# P19_M_2_KEY_M_SSD_WI-FI_BT.net
KiCad netlist of a schematic drawn in Altium Designer
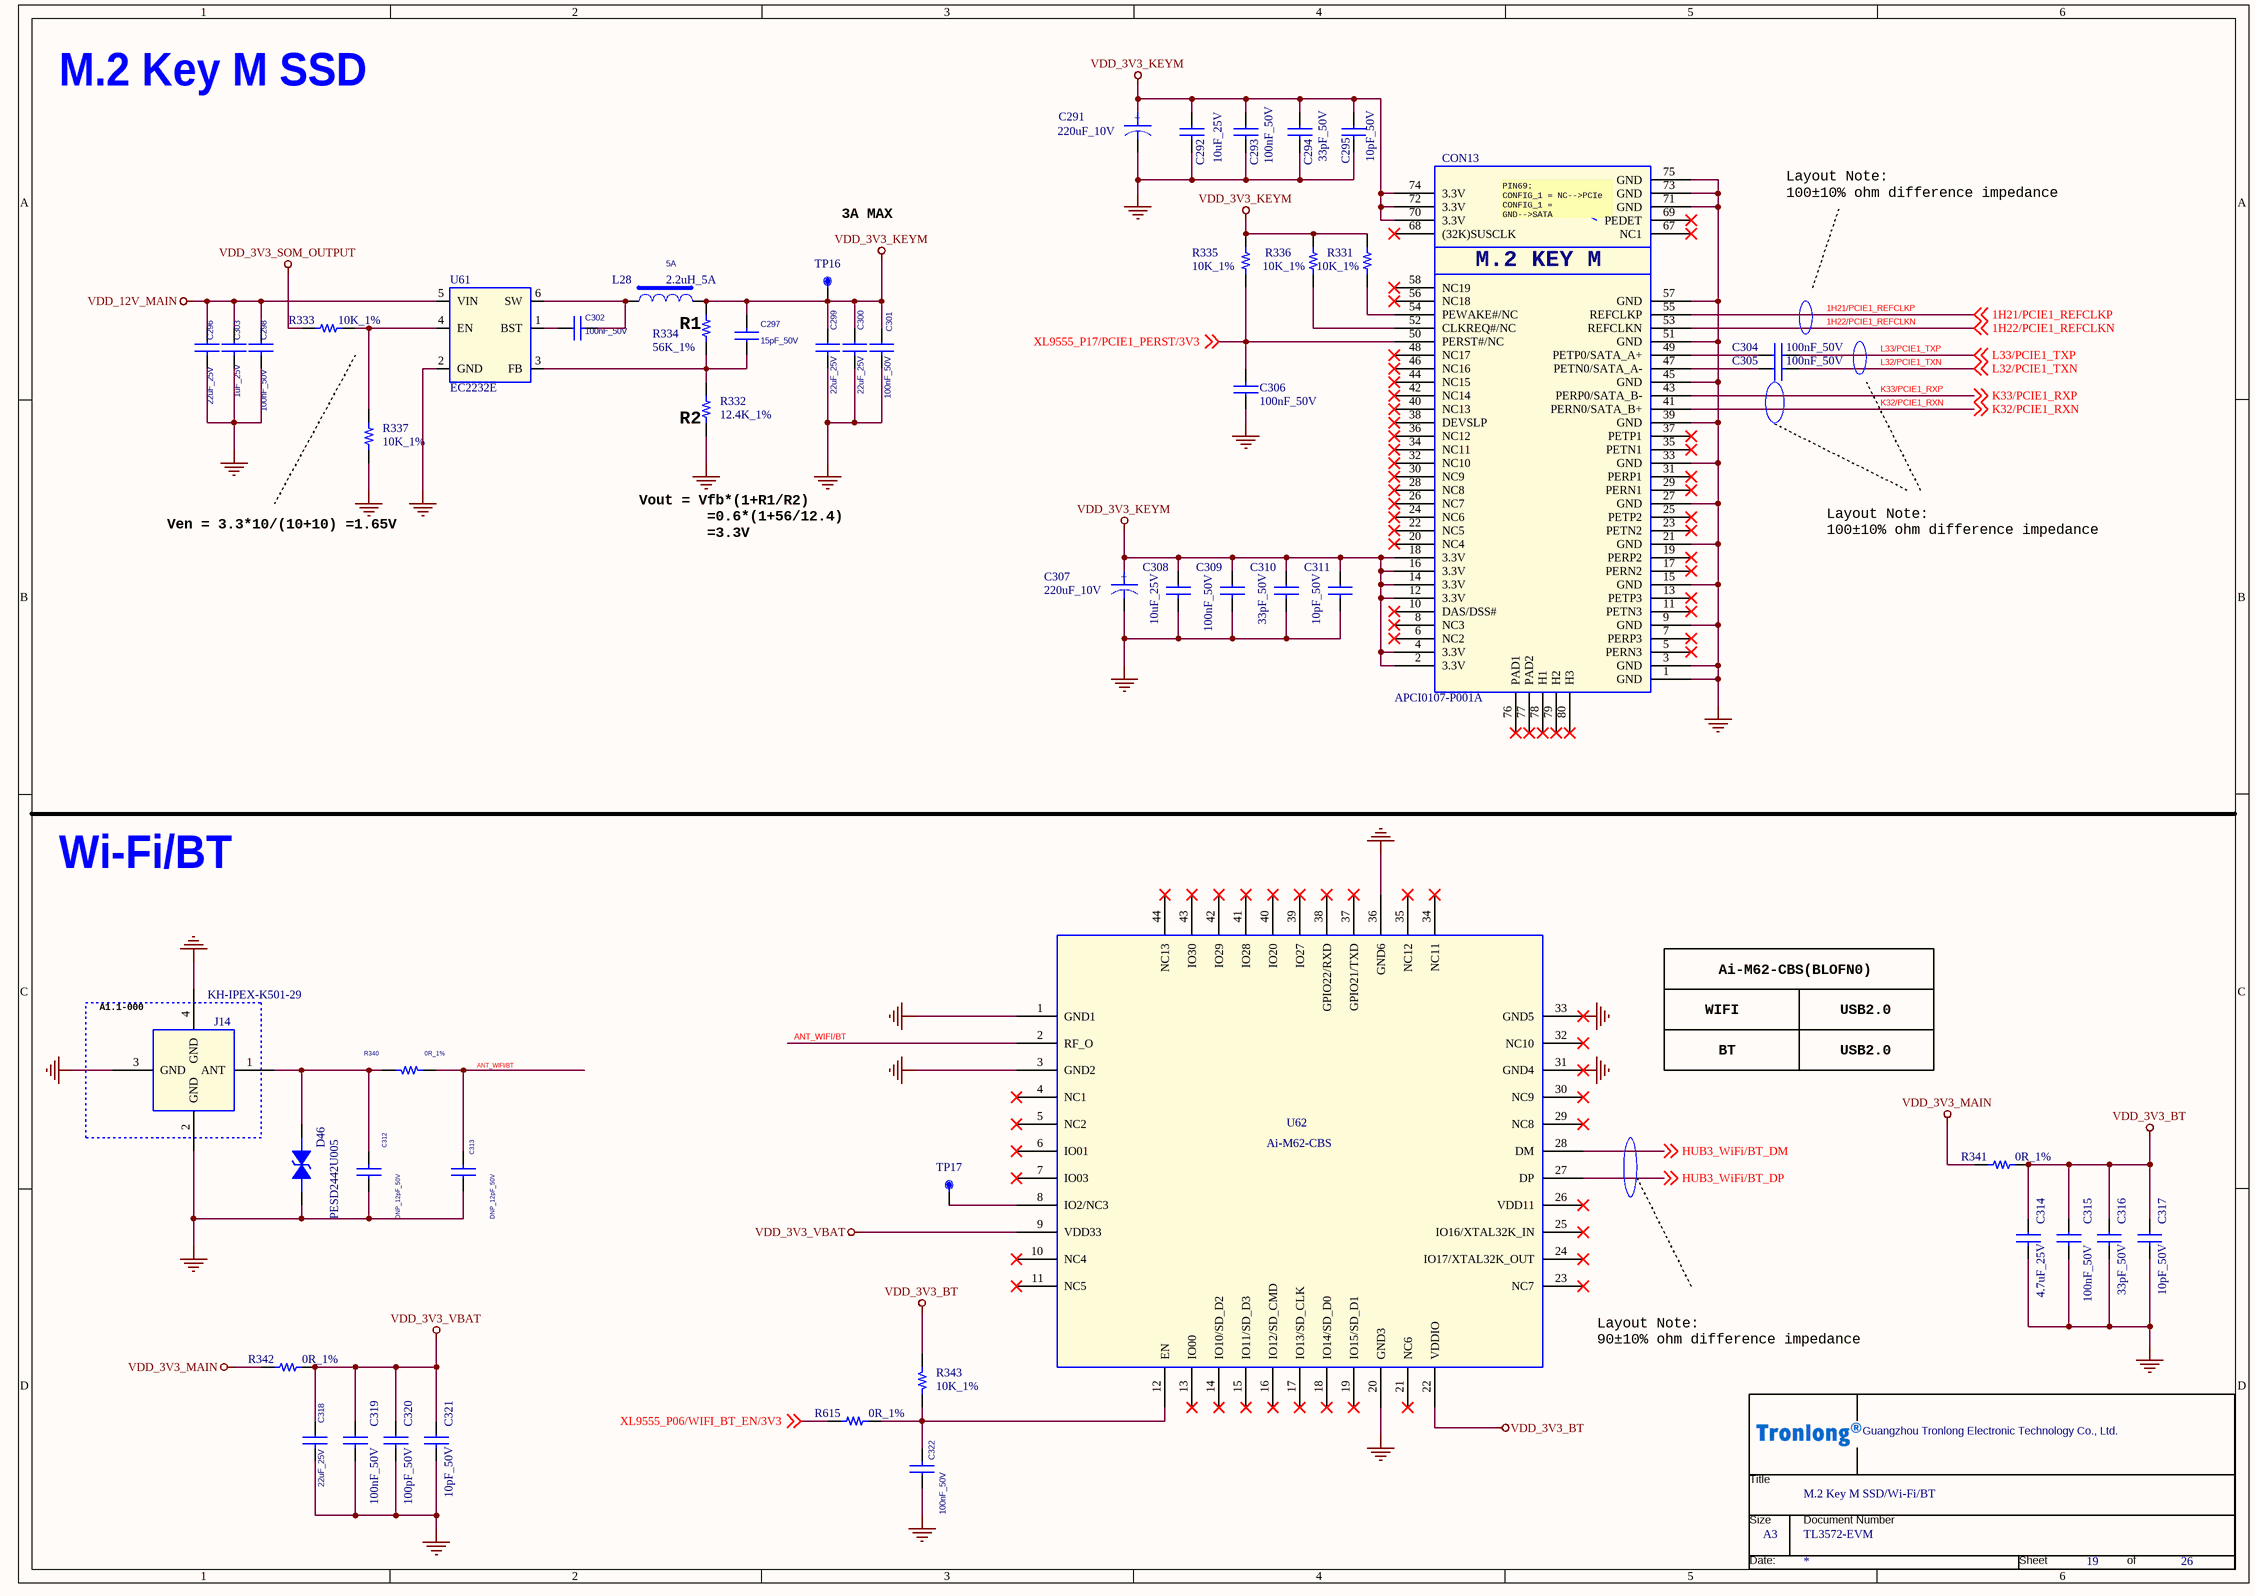
[diagram p0: P19_M.2 KEY M SSD_WI-FI_BT.SchDoc]

(export (version "E")
  (design (tool "Eeschema 10.0.6"))
  (components
    (comp (ref "C291")
      (value "220uF_10V")
      (footprint "CAP-CASE-D")
      (description "D型钽电容,220uF,10%,10V")
      (fields
        (field (name "MANUFACTURER") "湖南湘怡中元科技有限公司（XIANGYEE）")
        (field (name "MANUFACTURER PARTNUMBER") "CA45-D010K227T")
      )
      (libsource (lib "*") (part "CAP POL_Dup1"))
    )
    (comp (ref "C292")
      (value "10uF_25V")
      (footprint "C0603")
      (description "贴片陶瓷电容,10uF,20%,25V,X5R")
      (fields
        (field (name "MANUFACTURER PARTNUMBER") "0603X106M250NT")
        (field (name "MANUFACTURER") "广东风华高新科技股份有限公司（FH）")
      )
      (libsource (lib "*") (part "CAP NP_Dup2"))
    )
    (comp (ref "C293")
      (value "100nF_50V")
      (footprint "C0402")
      (description "贴片陶瓷电容,100nF,10%,50V,X7R")
      (fields
        (field (name "MANUFACTURER") "广东风华高新科技股份有限公司（FH）")
        (field (name "MANUFACTURER PARTNUMBER") "0402B104K500NT")
      )
      (libsource (lib "*") (part "CAP NP_Dup2"))
    )
    (comp (ref "C294")
      (value "33pF_50V")
      (footprint "C0402")
      (description "贴片陶瓷电容,33pF,5%,50V,COG")
      (fields
        (field (name "MANUFACTURER") "广东风华高新科技股份有限公司（FH）")
        (field (name "MANUFACTURER PARTNUMBER") "0402CG330J500NT")
      )
      (libsource (lib "*") (part "CAP NP_Dup2"))
    )
    (comp (ref "C295")
      (value "10pF_50V")
      (footprint "C0603")
      (description "CL10C100JB8NNNC,CC0603JRNPO9BN100,CC0603JRNP09BN100")
      (fields
        (field (name "MANUFACTURER") "广州创龙")
        (field (name "MANUFACTURER PARTNUMBER") "10pF,5%,C0603,50V,（X7R,X5R,COG,NPO或X7S）")
      )
      (libsource (lib "*") (part "CAP NP_Dup2"))
    )
    (comp (ref "C296")
      (value "22uF_25V")
      (footprint "C0805")
      (description "贴片陶瓷电容,22uF,20%,25V,X5R")
      (fields
        (field (name "MANUFACTURER PARTNUMBER") "0805X226M250NT")
        (field (name "MANUFACTURER") "广东风华高新科技股份有限公司（FH）")
      )
      (libsource (lib "*") (part "CAP NP_Dup2"))
    )
    (comp (ref "C297")
      (value "15pF_50V")
      (footprint "C0603")
      (description "CL10C150JB8NNNC,CC0603JRNPO9BN150")
      (fields
        (field (name "MANUFACTURER PARTNUMBER") "15pF,5%,C0603,50V,（X7R,X5R,COG,NPO或X7S）")
        (field (name "MANUFACTURER") "广州创龙")
      )
      (libsource (lib "*") (part "CAP NP_Dup2"))
    )
    (comp (ref "C298")
      (value "100nF_50V")
      (footprint "C0402")
      (description "贴片陶瓷电容,100nF,10%,50V,X7R")
      (fields
        (field (name "MANUFACTURER PARTNUMBER") "0402B104K500NT")
        (field (name "MANUFACTURER") "广东风华高新科技股份有限公司（FH）")
      )
      (libsource (lib "*") (part "CAP NP_Dup2"))
    )
    (comp (ref "C299")
      (value "22uF_25V")
      (footprint "C0805")
      (description "贴片陶瓷电容,22uF,20%,25V,X5R")
      (fields
        (field (name "MANUFACTURER PARTNUMBER") "0805X226M250NT")
        (field (name "MANUFACTURER") "广东风华高新科技股份有限公司（FH）")
      )
      (libsource (lib "*") (part "CAP NP_Dup2"))
    )
    (comp (ref "C300")
      (value "22uF_25V")
      (footprint "C0805")
      (description "贴片陶瓷电容,22uF,20%,25V,X5R")
      (fields
        (field (name "MANUFACTURER PARTNUMBER") "0805X226M250NT")
        (field (name "MANUFACTURER") "广东风华高新科技股份有限公司（FH）")
      )
      (libsource (lib "*") (part "CAP NP_Dup2"))
    )
    (comp (ref "C301")
      (value "100nF_50V")
      (footprint "C0402")
      (description "贴片陶瓷电容,100nF,10%,50V,X7R")
      (fields
        (field (name "MANUFACTURER PARTNUMBER") "0402B104K500NT")
        (field (name "MANUFACTURER") "广东风华高新科技股份有限公司（FH）")
      )
      (libsource (lib "*") (part "CAP NP_Dup2"))
    )
    (comp (ref "C302")
      (value "100nF_50V")
      (footprint "C0402")
      (description "贴片陶瓷电容,100nF,10%,50V,X7R")
      (fields
        (field (name "MANUFACTURER") "广东风华高新科技股份有限公司（FH）")
        (field (name "MANUFACTURER PARTNUMBER") "0402B104K500NT")
      )
      (libsource (lib "*") (part "CAP NP_Dup2"))
    )
    (comp (ref "C303")
      (value "1uF_25V")
      (footprint "C0402")
      (description "贴片陶瓷电容,1uF,10%,25V,X5R")
      (fields
        (field (name "MANUFACTURER") "广东风华高新科技股份有限公司（FH）")
        (field (name "MANUFACTURER PARTNUMBER") "0402X105K250NT")
      )
      (libsource (lib "*") (part "CAP NP_Dup2"))
    )
    (comp (ref "C304")
      (value "100nF_50V")
      (footprint "C0402")
      (description "贴片陶瓷电容,100nF,10%,50V,X7R")
      (fields (field (name "MANUFACTURER PARTNUMBER") "0402B104K500NT") (field (name "VOLTAGE") "50V"))
      (libsource (lib "*") (part "CAP NP_Dup2"))
    )
    (comp (ref "C305")
      (value "100nF_50V")
      (footprint "C0402")
      (description "贴片陶瓷电容,100nF,10%,50V,X7R")
      (fields (field (name "MANUFACTURER PARTNUMBER") "0402B104K500NT") (field (name "VOLTAGE") "50V"))
      (libsource (lib "*") (part "CAP NP_Dup2"))
    )
    (comp (ref "C306")
      (value "100nF_50V")
      (footprint "C0402")
      (description "贴片陶瓷电容,100nF,10%,50V,X7R")
      (fields
        (field (name "MANUFACTURER PARTNUMBER") "0402B104K500NT")
        (field (name "MANUFACTURER") "广东风华高新科技股份有限公司（FH）")
      )
      (libsource (lib "*") (part "CAP NP_Dup2"))
    )
    (comp (ref "C307")
      (value "220uF_10V")
      (footprint "CAP-CASE-D")
      (description "D型钽电容,220uF,10%,10V")
      (fields
        (field (name "MANUFACTURER PARTNUMBER") "CA45-D010K227T")
        (field (name "MANUFACTURER") "湖南湘怡中元科技有限公司（XIANGYEE）")
      )
      (libsource (lib "*") (part "CAP POL_Dup1"))
    )
    (comp (ref "C308")
      (value "10uF_25V")
      (footprint "C0603")
      (description "贴片陶瓷电容,10uF,20%,25V,X5R")
      (fields
        (field (name "MANUFACTURER PARTNUMBER") "0603X106M250NT")
        (field (name "MANUFACTURER") "广东风华高新科技股份有限公司（FH）")
      )
      (libsource (lib "*") (part "CAP NP_Dup2"))
    )
    (comp (ref "C309")
      (value "100nF_50V")
      (footprint "C0402")
      (description "贴片陶瓷电容,100nF,10%,50V,X7R")
      (fields
        (field (name "MANUFACTURER PARTNUMBER") "0402B104K500NT")
        (field (name "MANUFACTURER") "广东风华高新科技股份有限公司（FH）")
      )
      (libsource (lib "*") (part "CAP NP_Dup2"))
    )
    (comp (ref "C310")
      (value "33pF_50V")
      (footprint "C0402")
      (description "贴片陶瓷电容,33pF,5%,50V,COG")
      (fields
        (field (name "MANUFACTURER PARTNUMBER") "0402CG330J500NT")
        (field (name "MANUFACTURER") "广东风华高新科技股份有限公司（FH）")
      )
      (libsource (lib "*") (part "CAP NP_Dup2"))
    )
    (comp (ref "C311")
      (value "10pF_50V")
      (footprint "C0603")
      (description "CL10C100JB8NNNC,CC0603JRNPO9BN100,CC0603JRNP09BN100")
      (fields
        (field (name "MANUFACTURER PARTNUMBER") "10pF,5%,C0603,50V,（X7R,X5R,COG,NPO或X7S）")
        (field (name "MANUFACTURER") "广州创龙")
      )
      (libsource (lib "*") (part "CAP NP_Dup2"))
    )
    (comp (ref "C312")
      (value "DNP_12pF_50V")
      (footprint "C0402")
      (description "CL05C120JB5NNNC,CC0402JRNPO9BN120")
      (fields
        (field (name "MANUFACTURER") "广州创龙")
        (field (name "MANUFACTURER PARTNUMBER") "12pF,5%,C0402,50V,（X7R,X5R,COG,NPO或X7S）")
      )
      (libsource (lib "*") (part "CAP NP_Dup2"))
    )
    (comp (ref "C313")
      (value "DNP_12pF_50V")
      (footprint "C0402")
      (description "CL05C120JB5NNNC,CC0402JRNPO9BN120")
      (fields
        (field (name "MANUFACTURER") "广州创龙")
        (field (name "MANUFACTURER PARTNUMBER") "12pF,5%,C0402,50V,（X7R,X5R,COG,NPO或X7S）")
      )
      (libsource (lib "*") (part "CAP NP_Dup2"))
    )
    (comp (ref "C314")
      (value "4.7uF_25V")
      (footprint "C0603")
      (description "贴片陶瓷电容,4.7uF,10%,25V,X5R")
      (fields
        (field (name "MANUFACTURER PARTNUMBER") "0603X475K250NT")
        (field (name "MANUFACTURER") "广东风华高新科技股份有限公司（FH）")
      )
      (libsource (lib "*") (part "CAP NP_Dup3"))
    )
    (comp (ref "C315")
      (value "100nF_50V")
      (footprint "C0402")
      (description "贴片陶瓷电容,100nF,10%,50V,X7R")
      (fields
        (field (name "MANUFACTURER PARTNUMBER") "0402B104K500NT")
        (field (name "MANUFACTURER") "广东风华高新科技股份有限公司（FH）")
      )
      (libsource (lib "*") (part "CAP NP_Dup3"))
    )
    (comp (ref "C316")
      (value "33pF_50V")
      (footprint "C0402")
      (description "贴片陶瓷电容,33pF,5%,50V,COG")
      (fields
        (field (name "MANUFACTURER") "广东风华高新科技股份有限公司（FH）")
        (field (name "MANUFACTURER PARTNUMBER") "0402CG330J500NT")
      )
      (libsource (lib "*") (part "CAP NP_Dup2"))
    )
    (comp (ref "C317")
      (value "10pF_50V")
      (footprint "C0603")
      (description "CL10C100JB8NNNC,CC0603JRNPO9BN100,CC0603JRNP09BN100")
      (fields
        (field (name "MANUFACTURER") "广州创龙")
        (field (name "MANUFACTURER PARTNUMBER") "10pF,5%,C0603,50V,（X7R,X5R,COG,NPO或X7S）")
      )
      (libsource (lib "*") (part "CAP NP_Dup2"))
    )
    (comp (ref "C318")
      (value "22uF_25V")
      (footprint "C0805")
      (description "贴片陶瓷电容,22uF,20%,25V,X5R")
      (fields
        (field (name "MANUFACTURER") "广东风华高新科技股份有限公司（FH）")
        (field (name "MANUFACTURER PARTNUMBER") "0805X226M250NT")
      )
      (libsource (lib "*") (part "CAP NP_Dup2"))
    )
    (comp (ref "C319")
      (value "100nF_50V")
      (footprint "C0402")
      (description "贴片陶瓷电容,100nF,10%,50V,X7R")
      (fields
        (field (name "MANUFACTURER") "广东风华高新科技股份有限公司（FH）")
        (field (name "MANUFACTURER PARTNUMBER") "0402B104K500NT")
      )
      (libsource (lib "*") (part "CAP NP_Dup3"))
    )
    (comp (ref "C320")
      (value "100pF_50V")
      (footprint "C0402")
      (description "贴片陶瓷电容,100pF,5%,50V,COG")
      (fields
        (field (name "MANUFACTURER PARTNUMBER") "0402CG101J500NT")
        (field (name "MANUFACTURER") "广东风华高新科技股份有限公司（FH）")
        (field (name "CREATED BY") "JJJ")
      )
      (libsource (lib "*") (part "CAP NP_Dup3"))
    )
    (comp (ref "C321")
      (value "10pF_50V")
      (footprint "C0603")
      (description "CL10C100JB8NNNC,CC0603JRNPO9BN100,CC0603JRNP09BN100")
      (fields
        (field (name "MANUFACTURER PARTNUMBER") "10pF,5%,C0603,50V,（X7R,X5R,COG,NPO或X7S）")
        (field (name "MANUFACTURER") "广州创龙")
      )
      (libsource (lib "*") (part "CAP NP_Dup2"))
    )
    (comp (ref "C322")
      (value "100nF_50V")
      (footprint "C0402")
      (description "贴片陶瓷电容,100nF,10%,50V,X7R")
      (fields
        (field (name "MANUFACTURER PARTNUMBER") "0402B104K500NT")
        (field (name "MANUFACTURER") "广东风华高新科技股份有限公司（FH）")
      )
      (libsource (lib "*") (part "CAP NP_Dup2"))
    )
    (comp (ref "CON13")
      (value "APCI0107-P001A")
      (footprint "CON_SMD_APCI0113-P001A")
      (description "（M.2）金手指连接器，KEY M,0.5mm,H=4.2mm")
      (fields (field (name "MANUFACTURER") "深圳市连欣科技有限公司"))
      (libsource (lib "*") (part "M_2.2 KEY M"))
    )
    (comp (ref "D46")
      (value "PESD2442U005")
      (footprint "ESD_0402")
      (description "ESD二极管,VRWM=24V,VBR=300V,一组,双向,8KV,15KV")
      (fields (field (name "MANUFACTURER") "上海雷卯电子科技有限公司（Leiditech）"))
      (libsource (lib "*") (part "DIODE-TRIG"))
    )
    (comp (ref "J14")
      (value "KH-IPEX-K501-29")
      (footprint "IPEX1")
      (description "IPEX 1代连接器")
      (fields (field (name "MANUFACTURER") "深圳市金航标电子有限公司(kinghelm)"))
      (libsource (lib "*") (part "IPEX4"))
    )
    (comp (ref "L28")
      (value "2.2uH_5A")
      (footprint "SMD-L4040M-2P")
      (description "贴片功率电感,2.2uH,0.048Ω,Isat=7.6A,Irms=5A")
      (fields
        (field (name "MANUFACTURER") "深圳顺络电子股份有限公司（Sunlord）")
        (field (name "CURRENT") "5A")
        (field (name "MANUFACTURER PARTNUMBER") "WPN4020H2R2MT")
      )
      (libsource (lib "*") (part "INDUCTOR"))
    )
    (comp (ref "R331")
      (value "10K_1%")
      (footprint "R0402")
      (description "贴片电阻,10K,±1%,1/16W")
      (fields
        (field (name "MANUFACTURER PARTNUMBER") "RC-02K1002FT")
        (field (name "MANUFACTURER") "广东风华高新科技股份有限公司（FH）")
      )
      (libsource (lib "*") (part "Resistor_Dup3"))
    )
    (comp (ref "R332")
      (value "12.4K_1%")
      (footprint "R0402")
      (description "0402WGF1242TCE")
      (fields
        (field (name "MANUFACTURER") "广州创龙")
        (field (name "MANUFACTURER PARTNUMBER") "12.4K,±1%,R0402,≥1/16W")
      )
      (libsource (lib "*") (part "Resistor_Dup3"))
    )
    (comp (ref "R333")
      (value "10K_1%")
      (footprint "R0402")
      (description "贴片电阻,10K,±1%,1/16W")
      (fields
        (field (name "MANUFACTURER") "广东风华高新科技股份有限公司（FH）")
        (field (name "MANUFACTURER PARTNUMBER") "RC-02K1002FT")
      )
      (libsource (lib "*") (part "Resistor_Dup3"))
    )
    (comp (ref "R334")
      (value "56K_1%")
      (footprint "R0402")
      (description "RC0402FR-0756KL，0402WGF5602TCE")
      (fields
        (field (name "MANUFACTURER") "广州创龙")
        (field (name "MANUFACTURER PARTNUMBER") "56K,±1%,R0402,≥1/16W")
      )
      (libsource (lib "*") (part "Resistor_Dup3"))
    )
    (comp (ref "R335")
      (value "10K_1%")
      (footprint "R0402")
      (description "贴片电阻,10K,±1%,1/16W")
      (fields
        (field (name "MANUFACTURER") "广东风华高新科技股份有限公司（FH）")
        (field (name "MANUFACTURER PARTNUMBER") "RC-02K1002FT")
      )
      (libsource (lib "*") (part "Resistor_Dup3"))
    )
    (comp (ref "R336")
      (value "10K_1%")
      (footprint "R0402")
      (description "贴片电阻,10K,±1%,1/16W")
      (fields
        (field (name "MANUFACTURER") "广东风华高新科技股份有限公司（FH）")
        (field (name "MANUFACTURER PARTNUMBER") "RC-02K1002FT")
      )
      (libsource (lib "*") (part "Resistor_Dup3"))
    )
    (comp (ref "R337")
      (value "10K_1%")
      (footprint "R0402")
      (description "贴片电阻,10K,±1%,1/16W")
      (fields
        (field (name "MANUFACTURER PARTNUMBER") "RC-02K1002FT")
        (field (name "MANUFACTURER") "广东风华高新科技股份有限公司（FH）")
      )
      (libsource (lib "*") (part "Resistor_Dup3"))
    )
    (comp (ref "R340")
      (value "0R_1%")
      (footprint "R0402")
      (description "贴片电阻,0R,±1%,1/16W")
      (fields
        (field (name "MANUFACTURER PARTNUMBER") "RC-02000FT")
        (field (name "MANUFACTURER") "广东风华高新科技股份有限公司（FH）")
      )
      (libsource (lib "*") (part "Resistor_Dup3"))
    )
    (comp (ref "R341")
      (value "0R_1%")
      (footprint "R0603")
      (description "贴片电阻,0R,±1%,1/10W")
      (fields
        (field (name "MANUFACTURER PARTNUMBER") "RS-03000FT")
        (field (name "MANUFACTURER") "广东风华高新科技股份有限公司（FH）")
      )
      (libsource (lib "*") (part "Resistor_Dup3"))
    )
    (comp (ref "R342")
      (value "0R_1%")
      (footprint "R0603")
      (description "贴片电阻,0R,±1%,1/10W")
      (fields
        (field (name "MANUFACTURER") "广东风华高新科技股份有限公司（FH）")
        (field (name "MANUFACTURER PARTNUMBER") "RS-03000FT")
      )
      (libsource (lib "*") (part "Resistor_Dup3"))
    )
    (comp (ref "R343")
      (value "10K_1%")
      (footprint "R0402")
      (description "贴片电阻,10K,±1%,1/16W")
      (fields
        (field (name "MANUFACTURER") "广东风华高新科技股份有限公司（FH）")
        (field (name "MANUFACTURER PARTNUMBER") "RC-02K1002FT")
      )
      (libsource (lib "*") (part "Resistor_Dup3"))
    )
    (comp (ref "R615")
      (value "0R_1%")
      (footprint "R0603")
      (description "贴片电阻,0R,±1%,1/10W")
      (fields
        (field (name "MANUFACTURER PARTNUMBER") "RS-03000FT")
        (field (name "MANUFACTURER") "广东风华高新科技股份有限公司（FH）")
      )
      (libsource (lib "*") (part "Resistor_Dup3"))
    )
    (comp (ref "TP16")
      (value "SMT TP")
      (footprint "TP30")
      (description "/")
      (libsource (lib "*") (part "TP-S40"))
    )
    (comp (ref "TP17")
      (value "SMT TP")
      (footprint "TP30")
      (description "/")
      (libsource (lib "*") (part "TP-S40"))
    )
    (comp (ref "U61")
      (value "EC2232E")
      (footprint "SOT-23-6L")
      (description "DC/DC,Buck,Vin:4.5V~17V,Vout:0.6V~6V,3A,1路")
      (fields (field (name "MANUFACTURER") "上海芯强微电子股份有限公司（Ecranic）"))
      (libsource (lib "*") (part "WD1304E30"))
    )
    (comp (ref "U62")
      (value "Ai-M62-CBS")
      (footprint "FCS950U")
      (description "工业级WIFI & BT 二合一模块选型（USB通信）")
      (fields (field (name "MANUFACTURER") "QUECTEL"))
      (libsource (lib "*") (part "FCS950U_4"))
    )
  )
  (nets
    (net (code "1") (name "/ANT_WIFI{slash}BT") (class "Default")
      (node (ref "C313") (pin "2") (pinfunction "2_2") (pintype "passive"))
      (node (ref "R340") (pin "1") (pinfunction "1_1") (pintype "passive"))
      (node (ref "U62") (pin "2") (pinfunction "RF_O_2") (pintype "passive"))
    )
    (net (code "2") (name "1H21{slash}PCIE1_REFCLKP") (class "Default")
      (node (ref "CON13") (pin "55") (pinfunction "REFCLKP_55") (pintype "passive"))
    )
    (net (code "3") (name "1H22{slash}PCIE1_REFCLKN") (class "Default")
      (node (ref "CON13") (pin "53") (pinfunction "REFCLKN_53") (pintype "passive"))
    )
    (net (code "4") (name "GND") (class "Default")
      (node (ref "C291") (pin "2") (pinfunction "2_2") (pintype "passive"))
      (node (ref "C292") (pin "2") (pinfunction "2_2") (pintype "passive"))
      (node (ref "C293") (pin "2") (pinfunction "2_2") (pintype "passive"))
      (node (ref "C294") (pin "2") (pinfunction "2_2") (pintype "passive"))
      (node (ref "C295") (pin "2") (pinfunction "2_2") (pintype "passive"))
      (node (ref "C296") (pin "2") (pinfunction "2_2") (pintype "passive"))
      (node (ref "C298") (pin "2") (pinfunction "2_2") (pintype "passive"))
      (node (ref "C299") (pin "2") (pinfunction "2_2") (pintype "passive"))
      (node (ref "C300") (pin "2") (pinfunction "2_2") (pintype "passive"))
      (node (ref "C301") (pin "2") (pinfunction "2_2") (pintype "passive"))
      (node (ref "C303") (pin "2") (pinfunction "2_2") (pintype "passive"))
      (node (ref "C306") (pin "1") (pinfunction "1_1") (pintype "passive"))
      (node (ref "C307") (pin "2") (pinfunction "2_2") (pintype "passive"))
      (node (ref "C308") (pin "2") (pinfunction "2_2") (pintype "passive"))
      (node (ref "C309") (pin "2") (pinfunction "2_2") (pintype "passive"))
      (node (ref "C310") (pin "2") (pinfunction "2_2") (pintype "passive"))
      (node (ref "C311") (pin "2") (pinfunction "2_2") (pintype "passive"))
      (node (ref "C312") (pin "1") (pinfunction "1_1") (pintype "passive"))
      (node (ref "C313") (pin "1") (pinfunction "1_1") (pintype "passive"))
      (node (ref "C314") (pin "2") (pinfunction "2_2") (pintype "passive"))
      (node (ref "C315") (pin "2") (pinfunction "2_2") (pintype "passive"))
      (node (ref "C316") (pin "2") (pinfunction "2_2") (pintype "passive"))
      (node (ref "C317") (pin "2") (pinfunction "2_2") (pintype "passive"))
      (node (ref "C318") (pin "2") (pinfunction "2_2") (pintype "passive"))
      (node (ref "C319") (pin "2") (pinfunction "2_2") (pintype "passive"))
      (node (ref "C320") (pin "2") (pinfunction "2_2") (pintype "passive"))
      (node (ref "C321") (pin "2") (pinfunction "2_2") (pintype "passive"))
      (node (ref "C322") (pin "1") (pinfunction "1_1") (pintype "passive"))
      (node (ref "CON13") (pin "1") (pinfunction "GND_1") (pintype "power_in"))
      (node (ref "CON13") (pin "15") (pinfunction "GND_15") (pintype "power_in"))
      (node (ref "CON13") (pin "21") (pinfunction "GND_21") (pintype "power_in"))
      (node (ref "CON13") (pin "27") (pinfunction "GND_27") (pintype "power_in"))
      (node (ref "CON13") (pin "3") (pinfunction "GND_3") (pintype "power_in"))
      (node (ref "CON13") (pin "33") (pinfunction "GND_33") (pintype "power_in"))
      (node (ref "CON13") (pin "39") (pinfunction "GND_39") (pintype "power_in"))
      (node (ref "CON13") (pin "45") (pinfunction "GND_45") (pintype "power_in"))
      (node (ref "CON13") (pin "51") (pinfunction "GND_51") (pintype "power_in"))
      (node (ref "CON13") (pin "57") (pinfunction "GND_57") (pintype "power_in"))
      (node (ref "CON13") (pin "71") (pinfunction "GND_71") (pintype "power_in"))
      (node (ref "CON13") (pin "73") (pinfunction "GND_73") (pintype "power_in"))
      (node (ref "CON13") (pin "75") (pinfunction "GND_75") (pintype "power_in"))
      (node (ref "CON13") (pin "9") (pinfunction "GND_9") (pintype "power_in"))
      (node (ref "D46") (pin "1") (pinfunction "1_1") (pintype "passive"))
      (node (ref "J14") (pin "2") (pinfunction "GND_2") (pintype "power_in"))
      (node (ref "J14") (pin "3") (pinfunction "GND_3") (pintype "power_in"))
      (node (ref "J14") (pin "4") (pinfunction "GND_4") (pintype "power_in"))
      (node (ref "R332") (pin "1") (pinfunction "1_1") (pintype "passive"))
      (node (ref "R337") (pin "1") (pinfunction "1_1") (pintype "passive"))
      (node (ref "U61") (pin "2") (pinfunction "GND_2") (pintype "power_in"))
      (node (ref "U62") (pin "1") (pinfunction "GND1_1") (pintype "passive"))
      (node (ref "U62") (pin "20") (pinfunction "GND3_20") (pintype "passive"))
      (node (ref "U62") (pin "3") (pinfunction "GND2_3") (pintype "passive"))
      (node (ref "U62") (pin "31") (pinfunction "GND4_31") (pintype "passive"))
      (node (ref "U62") (pin "33") (pinfunction "GND5_33") (pintype "passive"))
      (node (ref "U62") (pin "36") (pinfunction "GND6_36") (pintype "passive"))
    )
    (net (code "5") (name "HUB3_WiFi{slash}BT_DM") (class "Default")
      (node (ref "U62") (pin "28") (pinfunction "DM_28") (pintype "passive"))
    )
    (net (code "6") (name "HUB3_WiFi{slash}BT_DP") (class "Default")
      (node (ref "U62") (pin "27") (pinfunction "DP_27") (pintype "passive"))
    )
    (net (code "7") (name "K32{slash}PCIE1_RXN") (class "Default")
      (node (ref "CON13") (pin "41") (pinfunction "PERN0/SATA_B+_41") (pintype "passive"))
    )
    (net (code "8") (name "K33{slash}PCIE1_RXP") (class "Default")
      (node (ref "CON13") (pin "43") (pinfunction "PERP0/SATA_B-_43") (pintype "passive"))
    )
    (net (code "9") (name "L32{slash}PCIE1_TXN") (class "Default")
      (node (ref "C305") (pin "2") (pinfunction "2_2") (pintype "passive"))
    )
    (net (code "10") (name "L33{slash}PCIE1_TXP") (class "Default")
      (node (ref "C304") (pin "2") (pinfunction "2_2") (pintype "passive"))
    )
    (net (code "11") (name "Net-(CON13-CLKREQ#{slash}NC)") (class "Default")
      (node (ref "CON13") (pin "52") (pinfunction "CLKREQ#/NC_52") (pintype "passive"))
      (node (ref "R336") (pin "2") (pinfunction "2_2") (pintype "passive"))
    )
    (net (code "12") (name "Net-(CON13-PETN0{slash}SATA_A-)") (class "Default")
      (node (ref "C305") (pin "1") (pinfunction "1_1") (pintype "passive"))
      (node (ref "CON13") (pin "47") (pinfunction "PETN0/SATA_A-_47") (pintype "passive"))
    )
    (net (code "13") (name "Net-(CON13-PETP0{slash}SATA_A+)") (class "Default")
      (node (ref "C304") (pin "1") (pinfunction "1_1") (pintype "passive"))
      (node (ref "CON13") (pin "49") (pinfunction "PETP0/SATA_A+_49") (pintype "passive"))
    )
    (net (code "14") (name "Net-(CON13-PEWAKE#{slash}NC)") (class "Default")
      (node (ref "CON13") (pin "54") (pinfunction "PEWAKE#/NC_54") (pintype "passive"))
      (node (ref "R331") (pin "2") (pinfunction "2_2") (pintype "passive"))
    )
    (net (code "15") (name "Net-(J14-ANT)") (class "Default")
      (node (ref "C312") (pin "2") (pinfunction "2_2") (pintype "passive"))
      (node (ref "D46") (pin "2") (pinfunction "2_2") (pintype "passive"))
      (node (ref "J14") (pin "1") (pinfunction "ANT_1") (pintype "passive"))
      (node (ref "R340") (pin "2") (pinfunction "2_2") (pintype "passive"))
    )
    (net (code "16") (name "Net-(U61-BST)") (class "Default")
      (node (ref "C302") (pin "1") (pinfunction "1_1") (pintype "passive"))
      (node (ref "U61") (pin "1") (pinfunction "BST_1") (pintype "passive"))
    )
    (net (code "17") (name "Net-(U61-EN)") (class "Default")
      (node (ref "R333") (pin "1") (pinfunction "1_1") (pintype "passive"))
      (node (ref "R337") (pin "2") (pinfunction "2_2") (pintype "passive"))
      (node (ref "U61") (pin "4") (pinfunction "EN_4") (pintype "passive"))
    )
    (net (code "18") (name "Net-(U61-FB)") (class "Default")
      (node (ref "C297") (pin "1") (pinfunction "1_1") (pintype "passive"))
      (node (ref "R332") (pin "2") (pinfunction "2_2") (pintype "passive"))
      (node (ref "R334") (pin "1") (pinfunction "1_1") (pintype "passive"))
      (node (ref "U61") (pin "3") (pinfunction "FB_3") (pintype "passive"))
    )
    (net (code "19") (name "Net-(U61-SW)") (class "Default")
      (node (ref "C302") (pin "2") (pinfunction "2_2") (pintype "passive"))
      (node (ref "L28") (pin "1") (pinfunction "1_1") (pintype "passive"))
      (node (ref "U61") (pin "6") (pinfunction "SW_6") (pintype "passive"))
    )
    (net (code "20") (name "Net-(U62-EN)") (class "Default")
      (node (ref "C322") (pin "2") (pinfunction "2_2") (pintype "passive"))
      (node (ref "R343") (pin "1") (pinfunction "1_1") (pintype "passive"))
      (node (ref "R615") (pin "2") (pinfunction "2_2") (pintype "passive"))
      (node (ref "U62") (pin "12") (pinfunction "EN_12") (pintype "passive"))
    )
    (net (code "21") (name "Net-(U62-IO2{slash}NC3)") (class "Default")
      (node (ref "TP17") (pin "1") (pinfunction "1_1") (pintype "passive"))
      (node (ref "U62") (pin "8") (pinfunction "IO2/NC3_8") (pintype "passive"))
    )
    (net (code "22") (name "VDD_3V3_BT") (class "Default")
      (node (ref "C314") (pin "1") (pinfunction "1_1") (pintype "passive"))
      (node (ref "C315") (pin "1") (pinfunction "1_1") (pintype "passive"))
      (node (ref "C316") (pin "1") (pinfunction "1_1") (pintype "passive"))
      (node (ref "C317") (pin "1") (pinfunction "1_1") (pintype "passive"))
      (node (ref "R341") (pin "2") (pinfunction "2_2") (pintype "passive"))
      (node (ref "R343") (pin "2") (pinfunction "2_2") (pintype "passive"))
      (node (ref "U62") (pin "22") (pinfunction "VDDIO_22") (pintype "passive"))
    )
    (net (code "23") (name "VDD_3V3_KEYM") (class "Default")
      (node (ref "C291") (pin "1") (pinfunction "1_1") (pintype "passive"))
      (node (ref "C292") (pin "1") (pinfunction "1_1") (pintype "passive"))
      (node (ref "C293") (pin "1") (pinfunction "1_1") (pintype "passive"))
      (node (ref "C294") (pin "1") (pinfunction "1_1") (pintype "passive"))
      (node (ref "C295") (pin "1") (pinfunction "1_1") (pintype "passive"))
      (node (ref "C297") (pin "2") (pinfunction "2_2") (pintype "passive"))
      (node (ref "C299") (pin "1") (pinfunction "1_1") (pintype "passive"))
      (node (ref "C300") (pin "1") (pinfunction "1_1") (pintype "passive"))
      (node (ref "C301") (pin "1") (pinfunction "1_1") (pintype "passive"))
      (node (ref "C307") (pin "1") (pinfunction "1_1") (pintype "passive"))
      (node (ref "C308") (pin "1") (pinfunction "1_1") (pintype "passive"))
      (node (ref "C309") (pin "1") (pinfunction "1_1") (pintype "passive"))
      (node (ref "C310") (pin "1") (pinfunction "1_1") (pintype "passive"))
      (node (ref "C311") (pin "1") (pinfunction "1_1") (pintype "passive"))
      (node (ref "CON13") (pin "12") (pinfunction "3.3V_12") (pintype "power_in"))
      (node (ref "CON13") (pin "14") (pinfunction "3.3V_14") (pintype "power_in"))
      (node (ref "CON13") (pin "16") (pinfunction "3.3V_16") (pintype "power_in"))
      (node (ref "CON13") (pin "18") (pinfunction "3.3V_18") (pintype "power_in"))
      (node (ref "CON13") (pin "2") (pinfunction "3.3V_2") (pintype "power_in"))
      (node (ref "CON13") (pin "4") (pinfunction "3.3V_4") (pintype "power_in"))
      (node (ref "CON13") (pin "70") (pinfunction "3.3V_70") (pintype "power_in"))
      (node (ref "CON13") (pin "72") (pinfunction "3.3V_72") (pintype "power_in"))
      (node (ref "CON13") (pin "74") (pinfunction "3.3V_74") (pintype "power_in"))
      (node (ref "L28") (pin "2") (pinfunction "2_2") (pintype "passive"))
      (node (ref "R331") (pin "1") (pinfunction "1_1") (pintype "passive"))
      (node (ref "R334") (pin "2") (pinfunction "2_2") (pintype "passive"))
      (node (ref "R335") (pin "1") (pinfunction "1_1") (pintype "passive"))
      (node (ref "R336") (pin "1") (pinfunction "1_1") (pintype "passive"))
      (node (ref "TP16") (pin "1") (pinfunction "1_1") (pintype "passive"))
    )
    (net (code "24") (name "VDD_3V3_MAIN") (class "Default")
      (node (ref "R341") (pin "1") (pinfunction "1_1") (pintype "passive"))
      (node (ref "R342") (pin "1") (pinfunction "1_1") (pintype "passive"))
    )
    (net (code "25") (name "VDD_3V3_SOM_OUTPUT") (class "Default")
      (node (ref "R333") (pin "2") (pinfunction "2_2") (pintype "passive"))
    )
    (net (code "26") (name "VDD_3V3_VBAT") (class "Default")
      (node (ref "C318") (pin "1") (pinfunction "1_1") (pintype "passive"))
      (node (ref "C319") (pin "1") (pinfunction "1_1") (pintype "passive"))
      (node (ref "C320") (pin "1") (pinfunction "1_1") (pintype "passive"))
      (node (ref "C321") (pin "1") (pinfunction "1_1") (pintype "passive"))
      (node (ref "R342") (pin "2") (pinfunction "2_2") (pintype "passive"))
      (node (ref "U62") (pin "9") (pinfunction "VDD33_9") (pintype "passive"))
    )
    (net (code "27") (name "VDD_12V_MAIN") (class "Default")
      (node (ref "C296") (pin "1") (pinfunction "1_1") (pintype "passive"))
      (node (ref "C298") (pin "1") (pinfunction "1_1") (pintype "passive"))
      (node (ref "C303") (pin "1") (pinfunction "1_1") (pintype "passive"))
      (node (ref "U61") (pin "5") (pinfunction "VIN_5") (pintype "power_in"))
    )
    (net (code "28") (name "XL9555_P06{slash}WIFI_BT_EN{slash}3V3") (class "Default")
      (node (ref "R615") (pin "1") (pinfunction "1_1") (pintype "passive"))
    )
    (net (code "29") (name "XL9555_P17{slash}PCIE1_PERST{slash}3V3") (class "Default")
      (node (ref "C306") (pin "2") (pinfunction "2_2") (pintype "passive"))
      (node (ref "CON13") (pin "50") (pinfunction "PERST#/NC_50") (pintype "passive"))
      (node (ref "R335") (pin "2") (pinfunction "2_2") (pintype "passive"))
    )
    (net (code "30") (name "unconnected-(CON13-(32K)SUSCLK-Pad68)") (class "Default")
      (node (ref "CON13") (pin "68") (pinfunction "(32K)SUSCLK_68") (pintype "passive+no_connect"))
    )
    (net (code "31") (name "unconnected-(CON13-DAS{slash}DSS#-Pad10)") (class "Default")
      (node (ref "CON13") (pin "10") (pinfunction "DAS/DSS#_10") (pintype "passive+no_connect"))
    )
    (net (code "32") (name "unconnected-(CON13-DEVSLP-Pad38)") (class "Default")
      (node (ref "CON13") (pin "38") (pinfunction "DEVSLP_38") (pintype "passive+no_connect"))
    )
    (net (code "33") (name "unconnected-(CON13-H1-Pad78)") (class "Default")
      (node (ref "CON13") (pin "78") (pinfunction "H1_78") (pintype "passive+no_connect"))
    )
    (net (code "34") (name "unconnected-(CON13-H2-Pad79)") (class "Default")
      (node (ref "CON13") (pin "79") (pinfunction "H2_79") (pintype "passive+no_connect"))
    )
    (net (code "35") (name "unconnected-(CON13-H3-Pad80)") (class "Default")
      (node (ref "CON13") (pin "80") (pinfunction "H3_80") (pintype "passive+no_connect"))
    )
    (net (code "36") (name "unconnected-(CON13-NC1-Pad67)") (class "Default")
      (node (ref "CON13") (pin "67") (pinfunction "NC1_67") (pintype "passive+no_connect"))
    )
    (net (code "37") (name "unconnected-(CON13-NC2-Pad6)") (class "Default")
      (node (ref "CON13") (pin "6") (pinfunction "NC2_6") (pintype "passive+no_connect"))
    )
    (net (code "38") (name "unconnected-(CON13-NC3-Pad8)") (class "Default")
      (node (ref "CON13") (pin "8") (pinfunction "NC3_8") (pintype "passive+no_connect"))
    )
    (net (code "39") (name "unconnected-(CON13-NC4-Pad20)") (class "Default")
      (node (ref "CON13") (pin "20") (pinfunction "NC4_20") (pintype "passive+no_connect"))
    )
    (net (code "40") (name "unconnected-(CON13-NC5-Pad22)") (class "Default")
      (node (ref "CON13") (pin "22") (pinfunction "NC5_22") (pintype "passive+no_connect"))
    )
    (net (code "41") (name "unconnected-(CON13-NC6-Pad24)") (class "Default")
      (node (ref "CON13") (pin "24") (pinfunction "NC6_24") (pintype "passive+no_connect"))
    )
    (net (code "42") (name "unconnected-(CON13-NC7-Pad26)") (class "Default")
      (node (ref "CON13") (pin "26") (pinfunction "NC7_26") (pintype "passive+no_connect"))
    )
    (net (code "43") (name "unconnected-(CON13-NC8-Pad28)") (class "Default")
      (node (ref "CON13") (pin "28") (pinfunction "NC8_28") (pintype "passive+no_connect"))
    )
    (net (code "44") (name "unconnected-(CON13-NC9-Pad30)") (class "Default")
      (node (ref "CON13") (pin "30") (pinfunction "NC9_30") (pintype "passive+no_connect"))
    )
    (net (code "45") (name "unconnected-(CON13-NC10-Pad32)") (class "Default")
      (node (ref "CON13") (pin "32") (pinfunction "NC10_32") (pintype "passive+no_connect"))
    )
    (net (code "46") (name "unconnected-(CON13-NC11-Pad34)") (class "Default")
      (node (ref "CON13") (pin "34") (pinfunction "NC11_34") (pintype "passive+no_connect"))
    )
    (net (code "47") (name "unconnected-(CON13-NC12-Pad36)") (class "Default")
      (node (ref "CON13") (pin "36") (pinfunction "NC12_36") (pintype "passive+no_connect"))
    )
    (net (code "48") (name "unconnected-(CON13-NC13-Pad40)") (class "Default")
      (node (ref "CON13") (pin "40") (pinfunction "NC13_40") (pintype "passive+no_connect"))
    )
    (net (code "49") (name "unconnected-(CON13-NC14-Pad42)") (class "Default")
      (node (ref "CON13") (pin "42") (pinfunction "NC14_42") (pintype "passive+no_connect"))
    )
    (net (code "50") (name "unconnected-(CON13-NC15-Pad44)") (class "Default")
      (node (ref "CON13") (pin "44") (pinfunction "NC15_44") (pintype "passive+no_connect"))
    )
    (net (code "51") (name "unconnected-(CON13-NC16-Pad46)") (class "Default")
      (node (ref "CON13") (pin "46") (pinfunction "NC16_46") (pintype "passive+no_connect"))
    )
    (net (code "52") (name "unconnected-(CON13-NC17-Pad48)") (class "Default")
      (node (ref "CON13") (pin "48") (pinfunction "NC17_48") (pintype "passive+no_connect"))
    )
    (net (code "53") (name "unconnected-(CON13-NC18-Pad56)") (class "Default")
      (node (ref "CON13") (pin "56") (pinfunction "NC18_56") (pintype "passive+no_connect"))
    )
    (net (code "54") (name "unconnected-(CON13-NC19-Pad58)") (class "Default")
      (node (ref "CON13") (pin "58") (pinfunction "NC19_58") (pintype "passive+no_connect"))
    )
    (net (code "55") (name "unconnected-(CON13-PAD1-Pad76)") (class "Default")
      (node (ref "CON13") (pin "76") (pinfunction "PAD1_76") (pintype "passive+no_connect"))
    )
    (net (code "56") (name "unconnected-(CON13-PAD2-Pad77)") (class "Default")
      (node (ref "CON13") (pin "77") (pinfunction "PAD2_77") (pintype "passive+no_connect"))
    )
    (net (code "57") (name "unconnected-(CON13-PEDET-Pad69)") (class "Default")
      (node (ref "CON13") (pin "69") (pinfunction "PEDET_69") (pintype "passive+no_connect"))
    )
    (net (code "58") (name "unconnected-(CON13-PERN1-Pad29)") (class "Default")
      (node (ref "CON13") (pin "29") (pinfunction "PERN1_29") (pintype "passive+no_connect"))
    )
    (net (code "59") (name "unconnected-(CON13-PERN2-Pad17)") (class "Default")
      (node (ref "CON13") (pin "17") (pinfunction "PERN2_17") (pintype "passive+no_connect"))
    )
    (net (code "60") (name "unconnected-(CON13-PERN3-Pad5)") (class "Default")
      (node (ref "CON13") (pin "5") (pinfunction "PERN3_5") (pintype "passive+no_connect"))
    )
    (net (code "61") (name "unconnected-(CON13-PERP1-Pad31)") (class "Default")
      (node (ref "CON13") (pin "31") (pinfunction "PERP1_31") (pintype "passive+no_connect"))
    )
    (net (code "62") (name "unconnected-(CON13-PERP2-Pad19)") (class "Default")
      (node (ref "CON13") (pin "19") (pinfunction "PERP2_19") (pintype "passive+no_connect"))
    )
    (net (code "63") (name "unconnected-(CON13-PERP3-Pad7)") (class "Default")
      (node (ref "CON13") (pin "7") (pinfunction "PERP3_7") (pintype "passive+no_connect"))
    )
    (net (code "64") (name "unconnected-(CON13-PETN1-Pad35)") (class "Default")
      (node (ref "CON13") (pin "35") (pinfunction "PETN1_35") (pintype "passive+no_connect"))
    )
    (net (code "65") (name "unconnected-(CON13-PETN2-Pad23)") (class "Default")
      (node (ref "CON13") (pin "23") (pinfunction "PETN2_23") (pintype "passive+no_connect"))
    )
    (net (code "66") (name "unconnected-(CON13-PETN3-Pad11)") (class "Default")
      (node (ref "CON13") (pin "11") (pinfunction "PETN3_11") (pintype "passive+no_connect"))
    )
    (net (code "67") (name "unconnected-(CON13-PETP1-Pad37)") (class "Default")
      (node (ref "CON13") (pin "37") (pinfunction "PETP1_37") (pintype "passive+no_connect"))
    )
    (net (code "68") (name "unconnected-(CON13-PETP2-Pad25)") (class "Default")
      (node (ref "CON13") (pin "25") (pinfunction "PETP2_25") (pintype "passive+no_connect"))
    )
    (net (code "69") (name "unconnected-(CON13-PETP3-Pad13)") (class "Default")
      (node (ref "CON13") (pin "13") (pinfunction "PETP3_13") (pintype "passive+no_connect"))
    )
    (net (code "70") (name "unconnected-(U62-GPIO21{slash}TXD-Pad37)") (class "Default")
      (node (ref "U62") (pin "37") (pinfunction "GPIO21/TXD_37") (pintype "passive+no_connect"))
    )
    (net (code "71") (name "unconnected-(U62-GPIO22{slash}RXD-Pad38)") (class "Default")
      (node (ref "U62") (pin "38") (pinfunction "GPIO22/RXD_38") (pintype "passive+no_connect"))
    )
    (net (code "72") (name "unconnected-(U62-IO00-Pad13)") (class "Default")
      (node (ref "U62") (pin "13") (pinfunction "IO00_13") (pintype "passive+no_connect"))
    )
    (net (code "73") (name "unconnected-(U62-IO01-Pad6)") (class "Default")
      (node (ref "U62") (pin "6") (pinfunction "IO01_6") (pintype "passive+no_connect"))
    )
    (net (code "74") (name "unconnected-(U62-IO03-Pad7)") (class "Default")
      (node (ref "U62") (pin "7") (pinfunction "IO03_7") (pintype "passive+no_connect"))
    )
    (net (code "75") (name "unconnected-(U62-IO10{slash}SD_D2-Pad14)") (class "Default")
      (node (ref "U62") (pin "14") (pinfunction "IO10/SD_D2_14") (pintype "passive+no_connect"))
    )
    (net (code "76") (name "unconnected-(U62-IO11{slash}SD_D3-Pad15)") (class "Default")
      (node (ref "U62") (pin "15") (pinfunction "IO11/SD_D3_15") (pintype "passive+no_connect"))
    )
    (net (code "77") (name "unconnected-(U62-IO12{slash}SD_CMD-Pad16)") (class "Default")
      (node (ref "U62") (pin "16") (pinfunction "IO12/SD_CMD_16") (pintype "passive+no_connect"))
    )
    (net (code "78") (name "unconnected-(U62-IO13{slash}SD_CLK-Pad17)") (class "Default")
      (node (ref "U62") (pin "17") (pinfunction "IO13/SD_CLK_17") (pintype "passive+no_connect"))
    )
    (net (code "79") (name "unconnected-(U62-IO14{slash}SD_D0-Pad18)") (class "Default")
      (node (ref "U62") (pin "18") (pinfunction "IO14/SD_D0_18") (pintype "passive+no_connect"))
    )
    (net (code "80") (name "unconnected-(U62-IO15{slash}SD_D1-Pad19)") (class "Default")
      (node (ref "U62") (pin "19") (pinfunction "IO15/SD_D1_19") (pintype "passive+no_connect"))
    )
    (net (code "81") (name "unconnected-(U62-IO16{slash}XTAL32K_IN-Pad25)") (class "Default")
      (node (ref "U62") (pin "25") (pinfunction "IO16/XTAL32K_IN_25") (pintype "passive+no_connect"))
    )
    (net (code "82") (name "unconnected-(U62-IO17{slash}XTAL32K_OUT-Pad24)") (class "Default")
      (node (ref "U62") (pin "24") (pinfunction "IO17/XTAL32K_OUT_24") (pintype "passive+no_connect"))
    )
    (net (code "83") (name "unconnected-(U62-IO20-Pad40)") (class "Default")
      (node (ref "U62") (pin "40") (pinfunction "IO20_40") (pintype "passive+no_connect"))
    )
    (net (code "84") (name "unconnected-(U62-IO27-Pad39)") (class "Default")
      (node (ref "U62") (pin "39") (pinfunction "IO27_39") (pintype "passive+no_connect"))
    )
    (net (code "85") (name "unconnected-(U62-IO28-Pad41)") (class "Default")
      (node (ref "U62") (pin "41") (pinfunction "IO28_41") (pintype "passive+no_connect"))
    )
    (net (code "86") (name "unconnected-(U62-IO29-Pad42)") (class "Default")
      (node (ref "U62") (pin "42") (pinfunction "IO29_42") (pintype "passive+no_connect"))
    )
    (net (code "87") (name "unconnected-(U62-IO30-Pad43)") (class "Default")
      (node (ref "U62") (pin "43") (pinfunction "IO30_43") (pintype "passive+no_connect"))
    )
    (net (code "88") (name "unconnected-(U62-NC1-Pad4)") (class "Default")
      (node (ref "U62") (pin "4") (pinfunction "NC1_4") (pintype "passive+no_connect"))
    )
    (net (code "89") (name "unconnected-(U62-NC2-Pad5)") (class "Default")
      (node (ref "U62") (pin "5") (pinfunction "NC2_5") (pintype "passive+no_connect"))
    )
    (net (code "90") (name "unconnected-(U62-NC4-Pad10)") (class "Default")
      (node (ref "U62") (pin "10") (pinfunction "NC4_10") (pintype "passive+no_connect"))
    )
    (net (code "91") (name "unconnected-(U62-NC5-Pad11)") (class "Default")
      (node (ref "U62") (pin "11") (pinfunction "NC5_11") (pintype "passive+no_connect"))
    )
    (net (code "92") (name "unconnected-(U62-NC6-Pad21)") (class "Default")
      (node (ref "U62") (pin "21") (pinfunction "NC6_21") (pintype "passive+no_connect"))
    )
    (net (code "93") (name "unconnected-(U62-NC7-Pad23)") (class "Default")
      (node (ref "U62") (pin "23") (pinfunction "NC7_23") (pintype "passive+no_connect"))
    )
    (net (code "94") (name "unconnected-(U62-NC8-Pad29)") (class "Default")
      (node (ref "U62") (pin "29") (pinfunction "NC8_29") (pintype "passive+no_connect"))
    )
    (net (code "95") (name "unconnected-(U62-NC9-Pad30)") (class "Default")
      (node (ref "U62") (pin "30") (pinfunction "NC9_30") (pintype "passive+no_connect"))
    )
    (net (code "96") (name "unconnected-(U62-NC10-Pad32)") (class "Default")
      (node (ref "U62") (pin "32") (pinfunction "NC10_32") (pintype "passive+no_connect"))
    )
    (net (code "97") (name "unconnected-(U62-NC11-Pad34)") (class "Default")
      (node (ref "U62") (pin "34") (pinfunction "NC11_34") (pintype "passive+no_connect"))
    )
    (net (code "98") (name "unconnected-(U62-NC12-Pad35)") (class "Default")
      (node (ref "U62") (pin "35") (pinfunction "NC12_35") (pintype "passive+no_connect"))
    )
    (net (code "99") (name "unconnected-(U62-NC13-Pad44)") (class "Default")
      (node (ref "U62") (pin "44") (pinfunction "NC13_44") (pintype "passive+no_connect"))
    )
    (net (code "100") (name "unconnected-(U62-VDD11-Pad26)") (class "Default")
      (node (ref "U62") (pin "26") (pinfunction "VDD11_26") (pintype "passive+no_connect"))
    )
  )
)
